# Power.net
KiCad netlist of a schematic drawn in Altium Designer
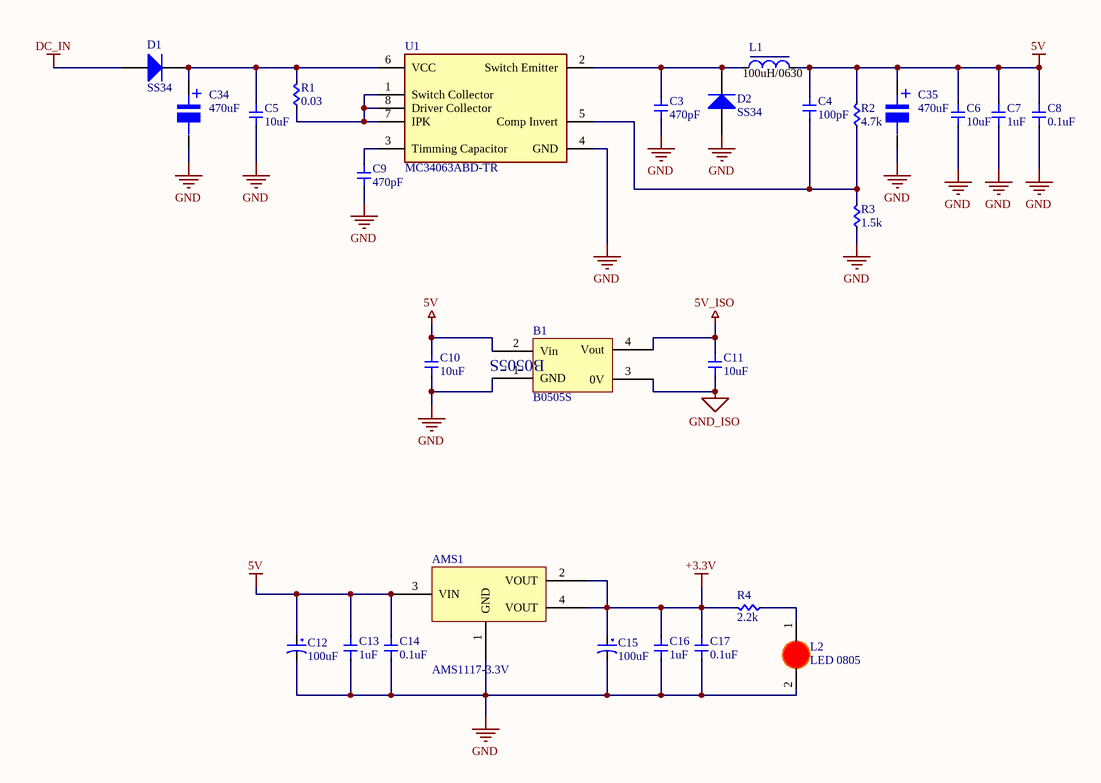
[diagram p0: Power.SchDoc]

(export (version "E")
  (design (tool "Eeschema 10.0.6"))
  (components
    (comp (ref "AMS1")
      (value "AMS1117-3.3V")
      (footprint "SOT223")
      (description "Dán")
      (libsource (lib "Altium_Lib_PTK") (part "AMS1117 SMD"))
    )
    (comp (ref "B1")
      (value "B0505S")
      (footprint "B0505S")
      (description "Cắm")
      (libsource (lib "Altium_Lib_PTK") (part "B0505S"))
    )
    (comp (ref "C3")
      (value "470pF")
      (footprint "Cap 0603")
      (description "Capacitor SMD 0603")
      (libsource (lib "Altium_Lib_PTK") (part "Cap 0603"))
    )
    (comp (ref "C4")
      (value "100pF")
      (footprint "Cap 0603")
      (description "Capacitor SMD 0603")
      (libsource (lib "Altium_Lib_PTK") (part "Cap 0603"))
    )
    (comp (ref "C5")
      (value "10uF")
      (footprint "Cap 1206")
      (description "Capacitor SMD 1206")
      (libsource (lib "Altium_Lib_PTK") (part "Cap 1206"))
    )
    (comp (ref "C6")
      (value "10uF")
      (footprint "Cap 1206")
      (description "Capacitor SMD 1206")
      (libsource (lib "Altium_Lib_PTK") (part "Cap 1206"))
    )
    (comp (ref "C7")
      (value "1uF")
      (footprint "Cap 0603")
      (description "Capacitor SMD 0603")
      (libsource (lib "Altium_Lib_PTK") (part "Cap 0603"))
    )
    (comp (ref "C8")
      (value "0.1uF")
      (footprint "Cap 0603")
      (description "Capacitor SMD 0603")
      (libsource (lib "Altium_Lib_PTK") (part "Cap 0603"))
    )
    (comp (ref "C9")
      (value "470pF")
      (footprint "Cap 0603")
      (description "Capacitor SMD 0603")
      (libsource (lib "Altium_Lib_PTK") (part "Cap 0603"))
    )
    (comp (ref "C10")
      (value "10uF")
      (footprint "Cap 1206")
      (description "Capacitor SMD 1206")
      (libsource (lib "Altium_Lib_PTK") (part "Cap 1206"))
    )
    (comp (ref "C11")
      (value "10uF")
      (footprint "Cap 1206")
      (description "Capacitor SMD 1206")
      (libsource (lib "Altium_Lib_PTK") (part "Cap 1206"))
    )
    (comp (ref "C12")
      (value "100uF")
      (footprint "tu tantalum smd7343")
      (description "Dán")
      (libsource (lib "Altium_Lib_PTK") (part "Tu tantalum 100uF 25V SMD7343"))
    )
    (comp (ref "C13")
      (value "1uF")
      (footprint "Cap 0603")
      (description "Capacitor SMD 0603")
      (libsource (lib "Altium_Lib_PTK") (part "Cap 0603"))
    )
    (comp (ref "C14")
      (value "0.1uF")
      (footprint "Cap 0603")
      (description "Capacitor SMD 0603")
      (libsource (lib "Altium_Lib_PTK") (part "Cap 0603"))
    )
    (comp (ref "C15")
      (value "100uF")
      (footprint "tu tantalum smd7343")
      (description "Dán")
      (libsource (lib "Altium_Lib_PTK") (part "Tu tantalum 100uF 25V SMD7343"))
    )
    (comp (ref "C16")
      (value "1uF")
      (footprint "Cap 0603")
      (description "Capacitor SMD 0603")
      (libsource (lib "Altium_Lib_PTK") (part "Cap 0603"))
    )
    (comp (ref "C17")
      (value "0.1uF")
      (footprint "Cap 0603")
      (description "Capacitor SMD 0603")
      (libsource (lib "Altium_Lib_PTK") (part "Cap 0603"))
    )
    (comp (ref "C34")
      (value "470uF")
      (footprint "tu nhom 8 (f)")
      (description "Dán")
      (libsource (lib "Altium_Lib_PTK") (part "Tu Nhom 470uF 16V"))
    )
    (comp (ref "C35")
      (value "470uF")
      (footprint "tu nhom 8 (f)")
      (description "Dán")
      (libsource (lib "Altium_Lib_PTK") (part "Tu Nhom 470uF 16V"))
    )
    (comp (ref "D1")
      (value "SS34")
      (footprint "DIODE SMA")
      (description "Dán")
      (libsource (lib "Altium_Lib_PTK") (part "Diode SS34 ( 1N5822 )"))
    )
    (comp (ref "D2")
      (value "SS34")
      (footprint "DIODE SMA")
      (description "Dán")
      (libsource (lib "Altium_Lib_PTK") (part "Diode SS34 ( 1N5822 )"))
    )
    (comp (ref "L1")
      (value "100uH/0630")
      (footprint "INDUCTOR_0630SMD")
      (description "Smd Inductors")
      (fields (field (name "PUBLISHER") "Altium Limited"))
      (libsource (lib "Altium_Lib_PTK") (part "Inductor Ferrite"))
    )
    (comp (ref "L2")
      (value "LED 0805")
      (footprint "LED-0805-Red")
      (description "Dán")
      (libsource (lib "Altium_Lib_PTK") (part "LED 0805 Do"))
    )
    (comp (ref "R1")
      (value "0.03")
      (footprint "RES 0805")
      (description "RES SMD 0805")
      (fields
        (field (name "MANUFACTURER") "Vishay Dale")
        (field (name "MANUFACTURER PART NUMBER") "CRCW040210K0FKED")
      )
      (libsource (lib "Altium_Lib_PTK") (part "RES 0805"))
    )
    (comp (ref "R2")
      (value "4.7k")
      (footprint "RES 0603")
      (description "RES SMD 0603")
      (fields
        (field (name "MANUFACTURER") "Vishay Dale")
        (field (name "MANUFACTURER PART NUMBER") "CRCW040210K0FKED")
      )
      (libsource (lib "Altium_Lib_PTK") (part "RES 0603"))
    )
    (comp (ref "R3")
      (value "1.5k")
      (footprint "RES 0603")
      (description "RES SMD 0603")
      (fields
        (field (name "MANUFACTURER") "Vishay Dale")
        (field (name "MANUFACTURER PART NUMBER") "CRCW040210K0FKED")
      )
      (libsource (lib "Altium_Lib_PTK") (part "RES 0603"))
    )
    (comp (ref "R4")
      (value "2.2k")
      (footprint "RES 0603")
      (description "RES SMD 0603")
      (fields
        (field (name "MANUFACTURER") "Vishay Dale")
        (field (name "MANUFACTURER PART NUMBER") "CRCW040210K0FKED")
      )
      (libsource (lib "Altium_Lib_PTK") (part "RES 0603"))
    )
    (comp (ref "U1")
      (value "MC34063ABD-TR")
      (footprint "SOP 8")
      (fields (field (name "MF") "STMicroelectronics"))
      (libsource (lib "Altium_Lib_PTK") (part "MC34063ABD-TR"))
    )
  )
  (nets
    (net (code "1") (name "+3.3V") (class "Default")
      (node (ref "AMS1") (pin "2") (pinfunction "VOUT_2") (pintype "passive"))
      (node (ref "AMS1") (pin "4") (pinfunction "VOUT_4") (pintype "passive"))
      (node (ref "C15") (pin "1") (pinfunction "1_1") (pintype "passive"))
      (node (ref "C16") (pin "1") (pinfunction "1_1") (pintype "passive"))
      (node (ref "C17") (pin "1") (pinfunction "1_1") (pintype "passive"))
      (node (ref "R4") (pin "2") (pinfunction "2_2") (pintype "passive"))
    )
    (net (code "2") (name "5V") (class "Default")
      (node (ref "AMS1") (pin "3") (pinfunction "VIN_3") (pintype "passive"))
      (node (ref "B1") (pin "2") (pinfunction "Vin_2") (pintype "passive"))
      (node (ref "C10") (pin "1") (pinfunction "1_1") (pintype "passive"))
      (node (ref "C12") (pin "1") (pinfunction "1_1") (pintype "passive"))
      (node (ref "C13") (pin "1") (pinfunction "1_1") (pintype "passive"))
      (node (ref "C14") (pin "1") (pinfunction "1_1") (pintype "passive"))
      (node (ref "C35") (pin "1") (pinfunction "1_1") (pintype "passive"))
      (node (ref "C4") (pin "1") (pinfunction "1_1") (pintype "passive"))
      (node (ref "C6") (pin "1") (pinfunction "1_1") (pintype "passive"))
      (node (ref "C7") (pin "1") (pinfunction "1_1") (pintype "passive"))
      (node (ref "C8") (pin "1") (pinfunction "1_1") (pintype "passive"))
      (node (ref "L1") (pin "2") (pinfunction "2_2") (pintype "passive"))
      (node (ref "R2") (pin "2") (pinfunction "2_2") (pintype "passive"))
    )
    (net (code "3") (name "5V_ISO") (class "Default")
      (node (ref "B1") (pin "4") (pinfunction "Vout_4") (pintype "passive"))
      (node (ref "C11") (pin "1") (pinfunction "1_1") (pintype "passive"))
    )
    (net (code "4") (name "DC_IN") (class "Default")
      (node (ref "D1") (pin "1") (pinfunction "A_1") (pintype "passive"))
    )
    (net (code "5") (name "GND") (class "Default")
      (node (ref "AMS1") (pin "1") (pinfunction "GND_1") (pintype "passive"))
      (node (ref "B1") (pin "1") (pinfunction "GND_1") (pintype "passive"))
      (node (ref "C10") (pin "2") (pinfunction "2_2") (pintype "passive"))
      (node (ref "C12") (pin "2") (pinfunction "2_2") (pintype "passive"))
      (node (ref "C13") (pin "2") (pinfunction "2_2") (pintype "passive"))
      (node (ref "C14") (pin "2") (pinfunction "2_2") (pintype "passive"))
      (node (ref "C15") (pin "2") (pinfunction "2_2") (pintype "passive"))
      (node (ref "C16") (pin "2") (pinfunction "2_2") (pintype "passive"))
      (node (ref "C17") (pin "2") (pinfunction "2_2") (pintype "passive"))
      (node (ref "C3") (pin "2") (pinfunction "2_2") (pintype "passive"))
      (node (ref "C34") (pin "2") (pinfunction "2_2") (pintype "passive"))
      (node (ref "C35") (pin "2") (pinfunction "2_2") (pintype "passive"))
      (node (ref "C5") (pin "2") (pinfunction "2_2") (pintype "passive"))
      (node (ref "C6") (pin "2") (pinfunction "2_2") (pintype "passive"))
      (node (ref "C7") (pin "2") (pinfunction "2_2") (pintype "passive"))
      (node (ref "C8") (pin "2") (pinfunction "2_2") (pintype "passive"))
      (node (ref "C9") (pin "2") (pinfunction "2_2") (pintype "passive"))
      (node (ref "D2") (pin "1") (pinfunction "A_1") (pintype "passive"))
      (node (ref "L2") (pin "2") (pinfunction "K_2") (pintype "passive"))
      (node (ref "R3") (pin "1") (pinfunction "1_1") (pintype "passive"))
      (node (ref "U1") (pin "4") (pinfunction "GND_4") (pintype "passive"))
    )
    (net (code "6") (name "GND_ISO") (class "Default")
      (node (ref "B1") (pin "3") (pinfunction "0V_3") (pintype "passive"))
      (node (ref "C11") (pin "2") (pinfunction "2_2") (pintype "passive"))
    )
    (net (code "7") (name "Net-(D1-K)") (class "Default")
      (node (ref "C34") (pin "1") (pinfunction "1_1") (pintype "passive"))
      (node (ref "C5") (pin "1") (pinfunction "1_1") (pintype "passive"))
      (node (ref "D1") (pin "2") (pinfunction "K_2") (pintype "passive"))
      (node (ref "R1") (pin "2") (pinfunction "2_2") (pintype "passive"))
      (node (ref "U1") (pin "6") (pinfunction "VCC_6") (pintype "power_in"))
    )
    (net (code "8") (name "Net-(D2-K)") (class "Default")
      (node (ref "C3") (pin "1") (pinfunction "1_1") (pintype "passive"))
      (node (ref "D2") (pin "2") (pinfunction "K_2") (pintype "passive"))
      (node (ref "L1") (pin "1") (pinfunction "1_1") (pintype "passive"))
      (node (ref "U1") (pin "2") (pinfunction "Switch_Emitter_2") (pintype "passive"))
    )
    (net (code "9") (name "Net-(L2-A)") (class "Default")
      (node (ref "L2") (pin "1") (pinfunction "A_1") (pintype "passive"))
      (node (ref "R4") (pin "1") (pinfunction "1_1") (pintype "passive"))
    )
    (net (code "10") (name "Net-(U1-Comp_Invert)") (class "Default")
      (node (ref "C4") (pin "2") (pinfunction "2_2") (pintype "passive"))
      (node (ref "R2") (pin "1") (pinfunction "1_1") (pintype "passive"))
      (node (ref "R3") (pin "2") (pinfunction "2_2") (pintype "passive"))
      (node (ref "U1") (pin "5") (pinfunction "Comp_Invert_5") (pintype "passive"))
    )
    (net (code "11") (name "Net-(U1-Driver_Collector)") (class "Default")
      (node (ref "R1") (pin "1") (pinfunction "1_1") (pintype "passive"))
      (node (ref "U1") (pin "1") (pinfunction "Switch_Collector_1") (pintype "passive"))
      (node (ref "U1") (pin "7") (pinfunction "IPK_7") (pintype "passive"))
      (node (ref "U1") (pin "8") (pinfunction "Driver_Collector_8") (pintype "passive"))
    )
    (net (code "12") (name "Net-(U1-Timming_Capacitor)") (class "Default")
      (node (ref "C9") (pin "1") (pinfunction "1_1") (pintype "passive"))
      (node (ref "U1") (pin "3") (pinfunction "Timming_Capacitor_3") (pintype "passive"))
    )
  )
)
